# 1_Main.net
KiCad netlist of a schematic drawn in EAGLE
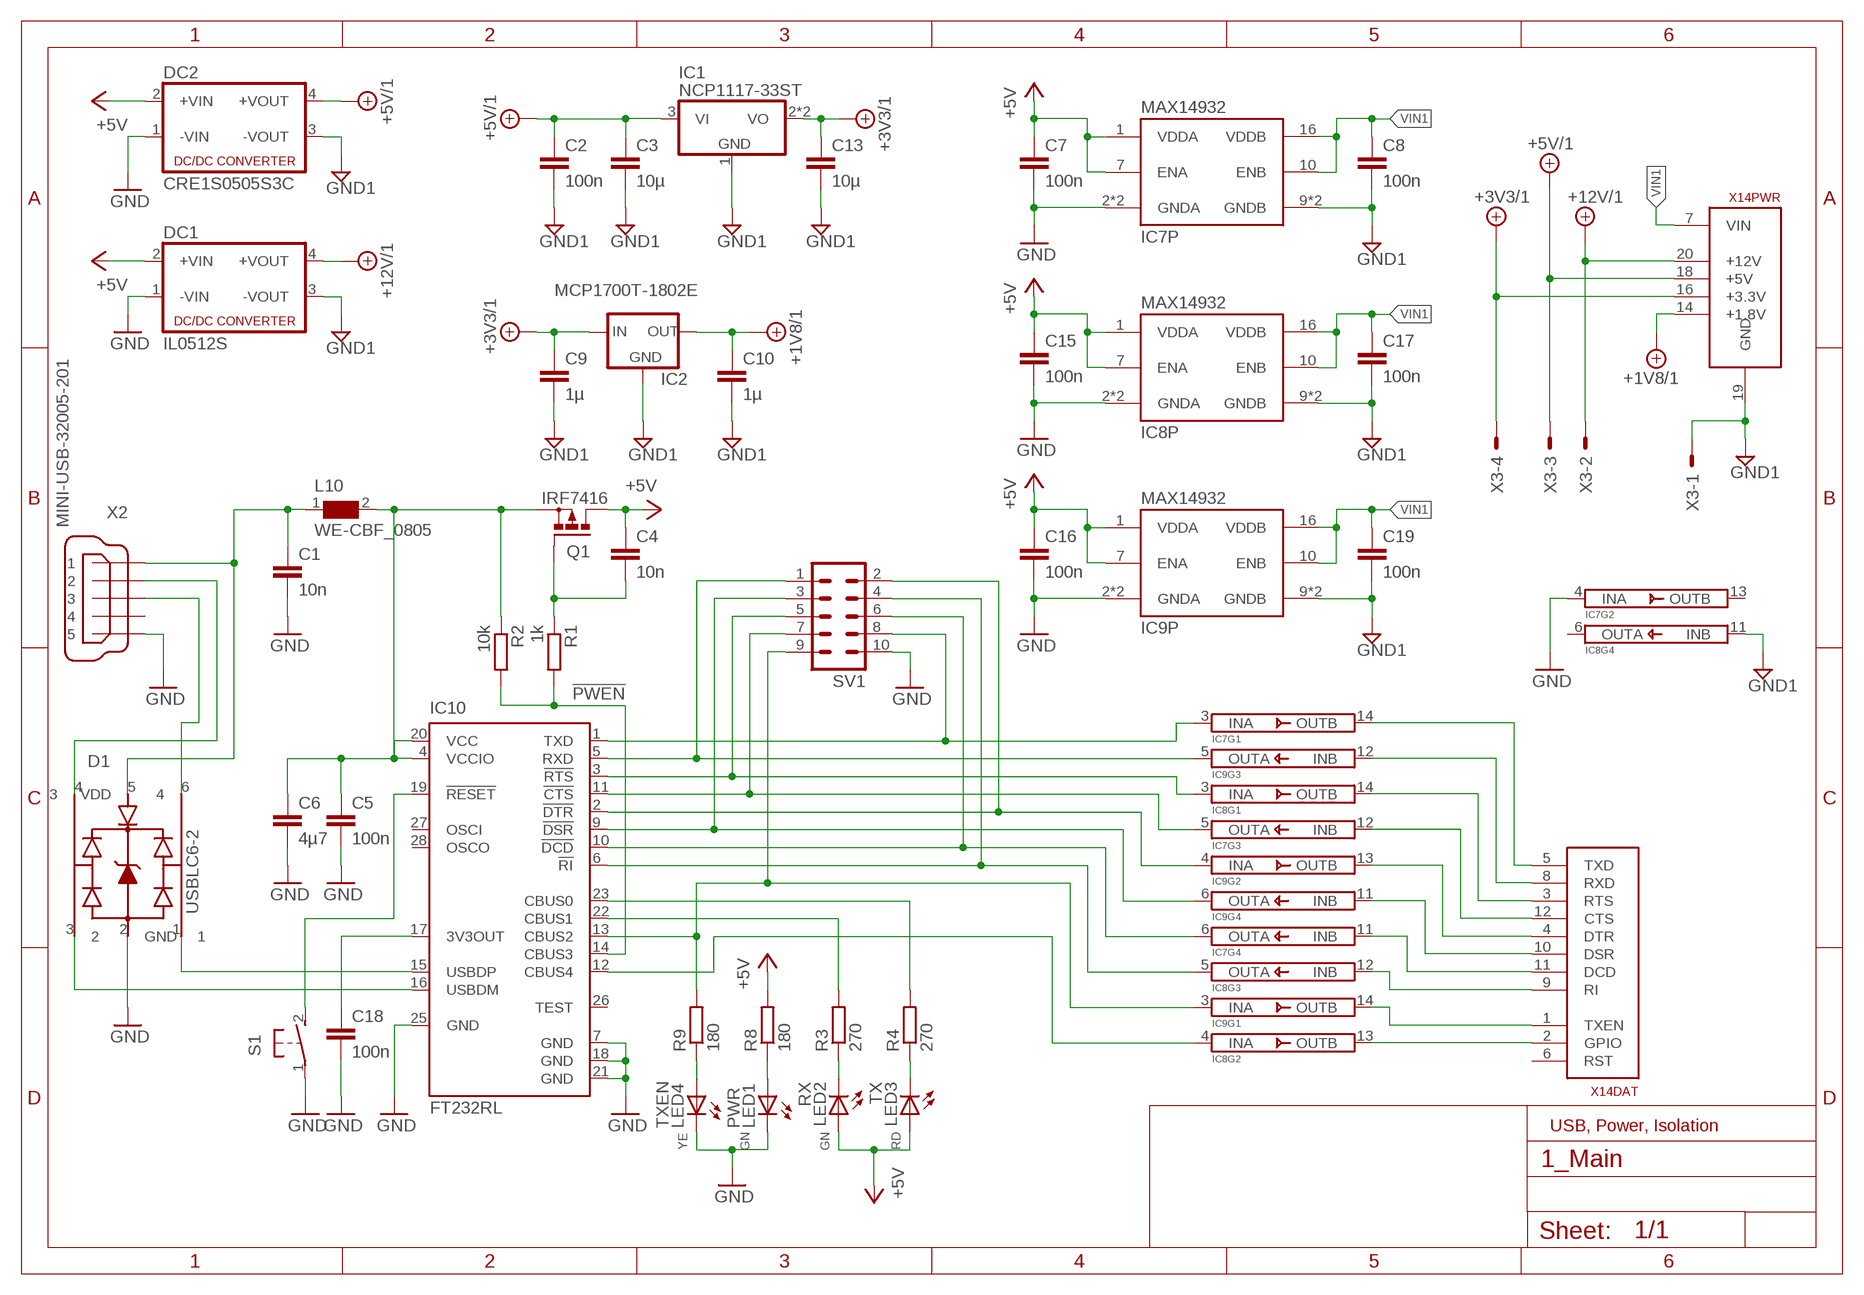
[diagram p0: schematic, sheet 1]

(export (version "E")
  (design (tool "Eeschema 10.0.6"))
  (components
    (comp (ref "C1")
      (value "10n")
      (footprint "eagle-import:C0805")
      (libsource (lib "eagle-import") (part "C-EUC0805"))
    )
    (comp (ref "C2")
      (value "100n")
      (footprint "eagle-import:C0805")
      (libsource (lib "eagle-import") (part "C-EUC0805"))
    )
    (comp (ref "C3")
      (value "10µ")
      (footprint "eagle-import:C0805")
      (libsource (lib "eagle-import") (part "C-EUC0805"))
    )
    (comp (ref "C4")
      (value "10n")
      (footprint "eagle-import:C0805")
      (libsource (lib "eagle-import") (part "C-EUC0805"))
    )
    (comp (ref "C5")
      (value "100n")
      (footprint "eagle-import:C0805")
      (libsource (lib "eagle-import") (part "C-EUC0805"))
    )
    (comp (ref "C6")
      (value "4µ7")
      (footprint "eagle-import:C0805")
      (libsource (lib "eagle-import") (part "C-EUC0805"))
    )
    (comp (ref "C7")
      (value "100n")
      (footprint "eagle-import:C0805")
      (libsource (lib "eagle-import") (part "C-EUC0805"))
    )
    (comp (ref "C8")
      (value "100n")
      (footprint "eagle-import:C0805")
      (libsource (lib "eagle-import") (part "C-EUC0805"))
    )
    (comp (ref "C9")
      (value "1µ")
      (footprint "eagle-import:C0805")
      (libsource (lib "eagle-import") (part "C-EUC0805"))
    )
    (comp (ref "C10")
      (value "1µ")
      (footprint "eagle-import:C0805")
      (libsource (lib "eagle-import") (part "C-EUC0805"))
    )
    (comp (ref "C13")
      (value "10µ")
      (footprint "eagle-import:C0805")
      (libsource (lib "eagle-import") (part "C-EUC0805"))
    )
    (comp (ref "C15")
      (value "100n")
      (footprint "eagle-import:C0805")
      (libsource (lib "eagle-import") (part "C-EUC0805"))
    )
    (comp (ref "C16")
      (value "100n")
      (footprint "eagle-import:C0805")
      (libsource (lib "eagle-import") (part "C-EUC0805"))
    )
    (comp (ref "C17")
      (value "100n")
      (footprint "eagle-import:C0805")
      (libsource (lib "eagle-import") (part "C-EUC0805"))
    )
    (comp (ref "C18")
      (value "100n")
      (footprint "eagle-import:C0805")
      (libsource (lib "eagle-import") (part "C-EUC0805"))
    )
    (comp (ref "C19")
      (value "100n")
      (footprint "eagle-import:C0805")
      (libsource (lib "eagle-import") (part "C-EUC0805"))
    )
    (comp (ref "D1")
      (value "USBLC6-2")
      (footprint "eagle-import:WE-TVS_SOT23-6L")
      (libsource (lib "eagle-import") (part "WE-TVS_82400102"))
    )
    (comp (ref "DC1")
      (value "IL0512S")
      (footprint "eagle-import:NME")
      (fields (field (name "MF") "C & D TECHNOLOGIES, INC") (field (name "MPN") "NME1205D"))
      (libsource (lib "eagle-import") (part "NME"))
    )
    (comp (ref "DC2")
      (value "CRE1S0505S3C")
      (footprint "eagle-import:NME")
      (fields (field (name "MF") "C & D TECHNOLOGIES, INC") (field (name "MPN") "NME1205D"))
      (libsource (lib "eagle-import") (part "NME"))
    )
    (comp (ref "IC1")
      (value "NCP1117-33ST")
      (footprint "eagle-import:SOT223")
      (libsource (lib "eagle-import") (part "NCP1117ST-33"))
    )
    (comp (ref "IC2")
      (value "MCP1700T-1802E")
      (footprint "eagle-import:SOT23")
      (libsource (lib "eagle-import") (part "MCP170X"))
    )
    (comp (ref "IC7")
      (value "MAX14932")
      (footprint "eagle-import:SO16")
      (libsource (lib "eagle-import") (part "MAX14932"))
    )
    (comp (ref "IC8")
      (value "MAX14932")
      (footprint "eagle-import:SO16")
      (libsource (lib "eagle-import") (part "MAX14932"))
    )
    (comp (ref "IC9")
      (value "MAX14932")
      (footprint "eagle-import:SO16")
      (libsource (lib "eagle-import") (part "MAX14932"))
    )
    (comp (ref "IC10")
      (value "FT232RL")
      (footprint "eagle-import:SSOP28")
      (libsource (lib "eagle-import") (part "FT232RL"))
    )
    (comp (ref "L10")
      (value "WE-CBF_0805")
      (footprint "eagle-import:0805")
      (libsource (lib "eagle-import") (part "WE-CBF_0805"))
    )
    (comp (ref "LED1")
      (value "PWR")
      (footprint "eagle-import:CHIPLED_0603")
      (fields (field (name "COLOR") "GN"))
      (libsource (lib "eagle-import") (part "LEDCHIPLED_0603"))
    )
    (comp (ref "LED2")
      (value "RX")
      (footprint "eagle-import:CHIPLED_0603")
      (fields (field (name "COLOR") "GN"))
      (libsource (lib "eagle-import") (part "LEDCHIPLED_0603"))
    )
    (comp (ref "LED3")
      (value "TX")
      (footprint "eagle-import:CHIPLED_0603")
      (fields (field (name "COLOR") "RD"))
      (libsource (lib "eagle-import") (part "LEDCHIPLED_0603"))
    )
    (comp (ref "LED4")
      (value "TXEN")
      (footprint "eagle-import:CHIPLED_0603")
      (fields (field (name "COLOR") "YE"))
      (libsource (lib "eagle-import") (part "LEDCHIPLED_0603"))
    )
    (comp (ref "Q1")
      (value "IRF7416")
      (footprint "eagle-import:SO-08")
      (libsource (lib "eagle-import") (part "P-MOSFET-SO8"))
    )
    (comp (ref "R1")
      (value "1k")
      (footprint "eagle-import:R0805")
      (libsource (lib "eagle-import") (part "R-EU_R0805"))
    )
    (comp (ref "R2")
      (value "10k")
      (footprint "eagle-import:R0805")
      (libsource (lib "eagle-import") (part "R-EU_R0805"))
    )
    (comp (ref "R3")
      (value "270")
      (footprint "eagle-import:R0805")
      (libsource (lib "eagle-import") (part "R-EU_R0805"))
    )
    (comp (ref "R4")
      (value "270")
      (footprint "eagle-import:R0805")
      (libsource (lib "eagle-import") (part "R-EU_R0805"))
    )
    (comp (ref "R8")
      (value "180")
      (footprint "eagle-import:R0805")
      (libsource (lib "eagle-import") (part "R-EU_R0805"))
    )
    (comp (ref "R9")
      (value "180")
      (footprint "eagle-import:R0805")
      (libsource (lib "eagle-import") (part "R-EU_R0805"))
    )
    (comp (ref "S1")
      (value "31-XX")
      (footprint "eagle-import:B3F-31XX")
      (fields (field (name "MPN") "B3F-3100"))
      (libsource (lib "eagle-import") (part "31-XX"))
    )
    (comp (ref "SV1")
      (value "ML10")
      (footprint "eagle-import:ML10")
      (libsource (lib "eagle-import") (part "ML10"))
    )
    (comp (ref "X2")
      (value "MINI-USB-32005-201")
      (footprint "eagle-import:32005-201")
      (libsource (lib "eagle-import") (part "MINI-USB-32005-201"))
    )
    (comp (ref "X3")
      (value "AKL18X-04W")
      (footprint "eagle-import:AKL182-04")
      (libsource (lib "eagle-import") (part "AKL18X-04W"))
    )
    (comp (ref "X14")
      (value "ALLSERIALMM")
      (footprint "eagle-import:MAIN-THT")
      (libsource (lib "eagle-import") (part "ALLSERIALMM"))
    )
  )
  (nets
    (net (code "1") (name "+1V8{slash}1") (class "Default")
      (node (ref "C10") (pin "1") (pinfunction "1_1") (pintype "passive"))
      (node (ref "IC2") (pin "2") (pinfunction "OUT_2") (pintype "passive"))
      (node (ref "X14") (pin "14") (pinfunction "+1.8V_14") (pintype "bidirectional"))
    )
    (net (code "2") (name "+3V3{slash}1") (class "Default")
      (node (ref "C13") (pin "1") (pinfunction "1_1") (pintype "passive"))
      (node (ref "C9") (pin "1") (pinfunction "1_1") (pintype "passive"))
      (node (ref "IC1") (pin "2") (pinfunction "VO_2") (pintype "passive"))
      (node (ref "IC1") (pin "4") (pinfunction "VO_4") (pintype "passive"))
      (node (ref "IC2") (pin "3") (pinfunction "IN_3") (pintype "input"))
      (node (ref "X14") (pin "16") (pinfunction "+3.3V_16") (pintype "bidirectional"))
      (node (ref "X3") (pin "P$4") (pinfunction "S_P$4") (pintype "passive"))
    )
    (net (code "3") (name "+5V") (class "Default")
      (node (ref "C15") (pin "1") (pinfunction "1_1") (pintype "passive"))
      (node (ref "C16") (pin "1") (pinfunction "1_1") (pintype "passive"))
      (node (ref "C4") (pin "1") (pinfunction "1_1") (pintype "passive"))
      (node (ref "C7") (pin "1") (pinfunction "1_1") (pintype "passive"))
      (node (ref "DC1") (pin "2") (pinfunction "+VIN_2") (pintype "passive"))
      (node (ref "DC2") (pin "2") (pinfunction "+VIN_2") (pintype "passive"))
      (node (ref "IC7") (pin "1") (pinfunction "VDDA_1") (pintype "power_in"))
      (node (ref "IC7") (pin "7") (pinfunction "ENA_7") (pintype "input"))
      (node (ref "IC8") (pin "1") (pinfunction "VDDA_1") (pintype "power_in"))
      (node (ref "IC8") (pin "7") (pinfunction "ENA_7") (pintype "input"))
      (node (ref "IC9") (pin "1") (pinfunction "VDDA_1") (pintype "power_in"))
      (node (ref "IC9") (pin "7") (pinfunction "ENA_7") (pintype "input"))
      (node (ref "LED2") (pin "A") (pinfunction "A_A") (pintype "passive"))
      (node (ref "LED3") (pin "A") (pinfunction "A_A") (pintype "passive"))
      (node (ref "Q1") (pin "5") (pinfunction "D_5") (pintype "passive"))
      (node (ref "Q1") (pin "6") (pinfunction "D_6") (pintype "passive"))
      (node (ref "Q1") (pin "7") (pinfunction "D_7") (pintype "passive"))
      (node (ref "Q1") (pin "8") (pinfunction "D_8") (pintype "passive"))
      (node (ref "R8") (pin "2") (pinfunction "2_2") (pintype "passive"))
    )
    (net (code "4") (name "+5V{slash}1") (class "Default")
      (node (ref "C2") (pin "1") (pinfunction "1_1") (pintype "passive"))
      (node (ref "C3") (pin "1") (pinfunction "1_1") (pintype "passive"))
      (node (ref "DC2") (pin "4") (pinfunction "+VOUT_4") (pintype "passive"))
      (node (ref "IC1") (pin "3") (pinfunction "VI_3") (pintype "input"))
      (node (ref "X14") (pin "18") (pinfunction "+5V_18") (pintype "bidirectional"))
      (node (ref "X3") (pin "P$3") (pinfunction "S_P$3") (pintype "passive"))
    )
    (net (code "5") (name "+12V{slash}1") (class "Default")
      (node (ref "DC1") (pin "4") (pinfunction "+VOUT_4") (pintype "passive"))
      (node (ref "X14") (pin "20") (pinfunction "+12V_20") (pintype "bidirectional"))
      (node (ref "X3") (pin "P$2") (pinfunction "S_P$2") (pintype "passive"))
    )
    (net (code "6") (name "/~{PWEN}") (class "Default")
      (node (ref "IC10") (pin "14") (pinfunction "CBUS3_14") (pintype "bidirectional"))
      (node (ref "R1") (pin "2") (pinfunction "2_2") (pintype "passive"))
      (node (ref "R2") (pin "2") (pinfunction "2_2") (pintype "passive"))
    )
    (net (code "7") (name "GND") (class "Default")
      (node (ref "C1") (pin "2") (pinfunction "2_2") (pintype "passive"))
      (node (ref "C15") (pin "2") (pinfunction "2_2") (pintype "passive"))
      (node (ref "C16") (pin "2") (pinfunction "2_2") (pintype "passive"))
      (node (ref "C18") (pin "2") (pinfunction "2_2") (pintype "passive"))
      (node (ref "C5") (pin "2") (pinfunction "2_2") (pintype "passive"))
      (node (ref "C6") (pin "2") (pinfunction "2_2") (pintype "passive"))
      (node (ref "C7") (pin "2") (pinfunction "2_2") (pintype "passive"))
      (node (ref "D1") (pin "2") (pinfunction "GND_2") (pintype "power_in"))
      (node (ref "DC1") (pin "1") (pinfunction "-VIN_1") (pintype "passive"))
      (node (ref "DC2") (pin "1") (pinfunction "-VIN_1") (pintype "passive"))
      (node (ref "IC10") (pin "18") (pinfunction "GND_18") (pintype "power_in"))
      (node (ref "IC10") (pin "21") (pinfunction "GND_21") (pintype "power_in"))
      (node (ref "IC10") (pin "25") (pinfunction "GND_25") (pintype "power_in"))
      (node (ref "IC10") (pin "7") (pinfunction "GND_7") (pintype "power_in"))
      (node (ref "IC7") (pin "2") (pinfunction "GNDA_2") (pintype "power_in"))
      (node (ref "IC7") (pin "4") (pinfunction "INA_4") (pintype "input"))
      (node (ref "IC7") (pin "8") (pinfunction "GNDA_8") (pintype "power_in"))
      (node (ref "IC8") (pin "2") (pinfunction "GNDA_2") (pintype "power_in"))
      (node (ref "IC8") (pin "8") (pinfunction "GNDA_8") (pintype "power_in"))
      (node (ref "IC9") (pin "2") (pinfunction "GNDA_2") (pintype "power_in"))
      (node (ref "IC9") (pin "8") (pinfunction "GNDA_8") (pintype "power_in"))
      (node (ref "LED1") (pin "C") (pinfunction "C_C") (pintype "passive"))
      (node (ref "LED4") (pin "C") (pinfunction "C_C") (pintype "passive"))
      (node (ref "S1") (pin "1") (pinfunction "P_1") (pintype "passive"))
      (node (ref "SV1") (pin "10") (pinfunction "10_10") (pintype "passive"))
      (node (ref "X2") (pin "5") (pinfunction "5_5") (pintype "passive"))
    )
    (net (code "8") (name "GND1") (class "Default")
      (node (ref "C10") (pin "2") (pinfunction "2_2") (pintype "passive"))
      (node (ref "C13") (pin "2") (pinfunction "2_2") (pintype "passive"))
      (node (ref "C17") (pin "2") (pinfunction "2_2") (pintype "passive"))
      (node (ref "C19") (pin "2") (pinfunction "2_2") (pintype "passive"))
      (node (ref "C2") (pin "2") (pinfunction "2_2") (pintype "passive"))
      (node (ref "C3") (pin "2") (pinfunction "2_2") (pintype "passive"))
      (node (ref "C8") (pin "2") (pinfunction "2_2") (pintype "passive"))
      (node (ref "C9") (pin "2") (pinfunction "2_2") (pintype "passive"))
      (node (ref "DC1") (pin "3") (pinfunction "-VOUT_3") (pintype "passive"))
      (node (ref "DC2") (pin "3") (pinfunction "-VOUT_3") (pintype "passive"))
      (node (ref "IC1") (pin "1") (pinfunction "GND_1") (pintype "passive"))
      (node (ref "IC2") (pin "1") (pinfunction "GND_1") (pintype "input"))
      (node (ref "IC7") (pin "15") (pinfunction "GNDB_15") (pintype "power_in"))
      (node (ref "IC7") (pin "9") (pinfunction "GNDB_9") (pintype "power_in"))
      (node (ref "IC8") (pin "11") (pinfunction "INB_11") (pintype "input"))
      (node (ref "IC8") (pin "15") (pinfunction "GNDB_15") (pintype "power_in"))
      (node (ref "IC8") (pin "9") (pinfunction "GNDB_9") (pintype "power_in"))
      (node (ref "IC9") (pin "15") (pinfunction "GNDB_15") (pintype "power_in"))
      (node (ref "IC9") (pin "9") (pinfunction "GNDB_9") (pintype "power_in"))
      (node (ref "X14") (pin "19") (pinfunction "GND_19") (pintype "bidirectional"))
      (node (ref "X3") (pin "P$1") (pinfunction "S_P$1") (pintype "passive"))
    )
    (net (code "9") (name "Net-(D1-2)") (class "Default")
      (node (ref "D1") (pin "3") (pinfunction "2_3") (pintype "passive"))
      (node (ref "IC10") (pin "16") (pinfunction "USBDM_16") (pintype "bidirectional"))
    )
    (net (code "10") (name "Net-(D1-3)") (class "Default")
      (node (ref "D1") (pin "4") (pinfunction "3_4") (pintype "passive"))
      (node (ref "X2") (pin "2") (pinfunction "2_2") (pintype "passive"))
    )
    (net (code "11") (name "Net-(D1-4)") (class "Default")
      (node (ref "D1") (pin "6") (pinfunction "4_6") (pintype "passive"))
      (node (ref "X2") (pin "3") (pinfunction "3_3") (pintype "passive"))
    )
    (net (code "12") (name "Net-(D1-VDD)") (class "Default")
      (node (ref "C1") (pin "1") (pinfunction "1_1") (pintype "passive"))
      (node (ref "D1") (pin "5") (pinfunction "VDD_5") (pintype "power_in"))
      (node (ref "L10") (pin "1") (pinfunction "1_1") (pintype "passive"))
      (node (ref "X2") (pin "1") (pinfunction "1_1") (pintype "passive"))
    )
    (net (code "13") (name "Net-(IC7A-OUTB)") (class "Default")
      (node (ref "IC7") (pin "14") (pinfunction "OUTB_14") (pintype "output"))
      (node (ref "X14") (pin "5") (pinfunction "TXD_5") (pintype "bidirectional"))
    )
    (net (code "14") (name "Net-(IC7C-INB)") (class "Default")
      (node (ref "IC7") (pin "12") (pinfunction "INB_12") (pintype "input"))
      (node (ref "X14") (pin "12") (pinfunction "CTS_12") (pintype "bidirectional"))
    )
    (net (code "15") (name "Net-(IC7D-INB)") (class "Default")
      (node (ref "IC7") (pin "11") (pinfunction "INB_11") (pintype "input"))
      (node (ref "X14") (pin "11") (pinfunction "DCD_11") (pintype "bidirectional"))
    )
    (net (code "16") (name "Net-(IC8A-OUTB)") (class "Default")
      (node (ref "IC8") (pin "14") (pinfunction "OUTB_14") (pintype "output"))
      (node (ref "X14") (pin "3") (pinfunction "RTS_3") (pintype "bidirectional"))
    )
    (net (code "17") (name "Net-(IC8B-OUTB)") (class "Default")
      (node (ref "IC8") (pin "13") (pinfunction "OUTB_13") (pintype "output"))
      (node (ref "X14") (pin "2") (pinfunction "GPIO_2") (pintype "bidirectional"))
    )
    (net (code "18") (name "Net-(IC8C-INB)") (class "Default")
      (node (ref "IC8") (pin "12") (pinfunction "INB_12") (pintype "input"))
      (node (ref "X14") (pin "9") (pinfunction "RI_9") (pintype "bidirectional"))
    )
    (net (code "19") (name "Net-(IC9A-OUTB)") (class "Default")
      (node (ref "IC9") (pin "14") (pinfunction "OUTB_14") (pintype "output"))
      (node (ref "X14") (pin "1") (pinfunction "TXEN_1") (pintype "bidirectional"))
    )
    (net (code "20") (name "Net-(IC9B-OUTB)") (class "Default")
      (node (ref "IC9") (pin "13") (pinfunction "OUTB_13") (pintype "output"))
      (node (ref "X14") (pin "4") (pinfunction "DTR_4") (pintype "bidirectional"))
    )
    (net (code "21") (name "Net-(IC9C-INB)") (class "Default")
      (node (ref "IC9") (pin "12") (pinfunction "INB_12") (pintype "input"))
      (node (ref "X14") (pin "8") (pinfunction "RXD_8") (pintype "bidirectional"))
    )
    (net (code "22") (name "Net-(IC9D-INB)") (class "Default")
      (node (ref "IC9") (pin "11") (pinfunction "INB_11") (pintype "input"))
      (node (ref "X14") (pin "10") (pinfunction "DSR_10") (pintype "bidirectional"))
    )
    (net (code "23") (name "Net-(IC10-3V3OUT)") (class "Default")
      (node (ref "C18") (pin "1") (pinfunction "1_1") (pintype "passive"))
      (node (ref "IC10") (pin "17") (pinfunction "3V3OUT_17") (pintype "output"))
    )
    (net (code "24") (name "Net-(IC10-CBUS0)") (class "Default")
      (node (ref "IC10") (pin "23") (pinfunction "CBUS0_23") (pintype "bidirectional"))
      (node (ref "R4") (pin "2") (pinfunction "2_2") (pintype "passive"))
    )
    (net (code "25") (name "Net-(IC10-CBUS1)") (class "Default")
      (node (ref "IC10") (pin "22") (pinfunction "CBUS1_22") (pintype "bidirectional"))
      (node (ref "R3") (pin "2") (pinfunction "2_2") (pintype "passive"))
    )
    (net (code "26") (name "Net-(IC10-CBUS2)") (class "Default")
      (node (ref "IC10") (pin "13") (pinfunction "CBUS2_13") (pintype "bidirectional"))
      (node (ref "IC9") (pin "3") (pinfunction "INA_3") (pintype "input"))
      (node (ref "R9") (pin "2") (pinfunction "2_2") (pintype "passive"))
      (node (ref "SV1") (pin "9") (pinfunction "9_9") (pintype "passive"))
    )
    (net (code "27") (name "Net-(IC10-CBUS4)") (class "Default")
      (node (ref "IC10") (pin "12") (pinfunction "CBUS4_12") (pintype "bidirectional"))
      (node (ref "IC8") (pin "4") (pinfunction "INA_4") (pintype "input"))
    )
    (net (code "28") (name "Net-(IC10-RXD)") (class "Default")
      (node (ref "IC10") (pin "5") (pinfunction "RXD_5") (pintype "input"))
      (node (ref "IC9") (pin "5") (pinfunction "OUTA_5") (pintype "output"))
      (node (ref "SV1") (pin "1") (pinfunction "1_1") (pintype "passive"))
    )
    (net (code "29") (name "Net-(IC10-TXD)") (class "Default")
      (node (ref "IC10") (pin "1") (pinfunction "TXD_1") (pintype "output"))
      (node (ref "IC7") (pin "3") (pinfunction "INA_3") (pintype "input"))
      (node (ref "SV1") (pin "8") (pinfunction "8_8") (pintype "passive"))
    )
    (net (code "30") (name "Net-(IC10-USBDP)") (class "Default")
      (node (ref "D1") (pin "1") (pinfunction "1_1") (pintype "passive"))
      (node (ref "IC10") (pin "15") (pinfunction "USBDP_15") (pintype "bidirectional"))
    )
    (net (code "31") (name "Net-(IC10-VCC)") (class "Default")
      (node (ref "C5") (pin "1") (pinfunction "1_1") (pintype "passive"))
      (node (ref "C6") (pin "1") (pinfunction "1_1") (pintype "passive"))
      (node (ref "IC10") (pin "20") (pinfunction "VCC_20") (pintype "power_in"))
      (node (ref "IC10") (pin "4") (pinfunction "VCCIO_4") (pintype "power_in"))
      (node (ref "L10") (pin "2") (pinfunction "2_2") (pintype "passive"))
      (node (ref "Q1") (pin "1") (pinfunction "S_1") (pintype "passive"))
      (node (ref "Q1") (pin "2") (pinfunction "S_2") (pintype "passive"))
      (node (ref "Q1") (pin "3") (pinfunction "S_3") (pintype "passive"))
      (node (ref "R2") (pin "1") (pinfunction "1_1") (pintype "passive"))
    )
    (net (code "32") (name "Net-(IC10-~{CTS})") (class "Default")
      (node (ref "IC10") (pin "11") (pinfunction "~{CTS}_11") (pintype "input"))
      (node (ref "IC7") (pin "5") (pinfunction "OUTA_5") (pintype "output"))
      (node (ref "SV1") (pin "7") (pinfunction "7_7") (pintype "passive"))
    )
    (net (code "33") (name "Net-(IC10-~{DCD})") (class "Default")
      (node (ref "IC10") (pin "10") (pinfunction "~{DCD}_10") (pintype "input"))
      (node (ref "IC7") (pin "6") (pinfunction "OUTA_6") (pintype "output"))
      (node (ref "SV1") (pin "6") (pinfunction "6_6") (pintype "passive"))
    )
    (net (code "34") (name "Net-(IC10-~{DSR})") (class "Default")
      (node (ref "IC10") (pin "9") (pinfunction "~{DSR}_9") (pintype "input"))
      (node (ref "IC9") (pin "6") (pinfunction "OUTA_6") (pintype "output"))
      (node (ref "SV1") (pin "3") (pinfunction "3_3") (pintype "passive"))
    )
    (net (code "35") (name "Net-(IC10-~{DTR})") (class "Default")
      (node (ref "IC10") (pin "2") (pinfunction "~{DTR}_2") (pintype "output"))
      (node (ref "IC9") (pin "4") (pinfunction "INA_4") (pintype "input"))
      (node (ref "SV1") (pin "2") (pinfunction "2_2") (pintype "passive"))
    )
    (net (code "36") (name "Net-(IC10-~{RESET})") (class "Default")
      (node (ref "IC10") (pin "19") (pinfunction "~{RESET}_19") (pintype "input"))
      (node (ref "S1") (pin "2") (pinfunction "S_2") (pintype "passive"))
    )
    (net (code "37") (name "Net-(IC10-~{RI})") (class "Default")
      (node (ref "IC10") (pin "6") (pinfunction "~{RI}_6") (pintype "input"))
      (node (ref "IC8") (pin "5") (pinfunction "OUTA_5") (pintype "output"))
      (node (ref "SV1") (pin "4") (pinfunction "4_4") (pintype "passive"))
    )
    (net (code "38") (name "Net-(IC10-~{RTS})") (class "Default")
      (node (ref "IC10") (pin "3") (pinfunction "~{RTS}_3") (pintype "output"))
      (node (ref "IC8") (pin "3") (pinfunction "INA_3") (pintype "input"))
      (node (ref "SV1") (pin "5") (pinfunction "5_5") (pintype "passive"))
    )
    (net (code "39") (name "Net-(LED1-PadA)") (class "Default")
      (node (ref "LED1") (pin "A") (pinfunction "A_A") (pintype "passive"))
      (node (ref "R8") (pin "1") (pinfunction "1_1") (pintype "passive"))
    )
    (net (code "40") (name "Net-(LED2-PadC)") (class "Default")
      (node (ref "LED2") (pin "C") (pinfunction "C_C") (pintype "passive"))
      (node (ref "R3") (pin "1") (pinfunction "1_1") (pintype "passive"))
    )
    (net (code "41") (name "Net-(LED3-PadC)") (class "Default")
      (node (ref "LED3") (pin "C") (pinfunction "C_C") (pintype "passive"))
      (node (ref "R4") (pin "1") (pinfunction "1_1") (pintype "passive"))
    )
    (net (code "42") (name "Net-(LED4-PadA)") (class "Default")
      (node (ref "LED4") (pin "A") (pinfunction "A_A") (pintype "passive"))
      (node (ref "R9") (pin "1") (pinfunction "1_1") (pintype "passive"))
    )
    (net (code "43") (name "Net-(Q1-G)") (class "Default")
      (node (ref "C4") (pin "2") (pinfunction "2_2") (pintype "passive"))
      (node (ref "Q1") (pin "4") (pinfunction "G_4") (pintype "passive"))
      (node (ref "R1") (pin "1") (pinfunction "1_1") (pintype "passive"))
    )
    (net (code "44") (name "VIN1") (class "Default")
      (node (ref "C17") (pin "1") (pinfunction "1_1") (pintype "passive"))
      (node (ref "C19") (pin "1") (pinfunction "1_1") (pintype "passive"))
      (node (ref "C8") (pin "1") (pinfunction "1_1") (pintype "passive"))
      (node (ref "IC7") (pin "10") (pinfunction "ENB_10") (pintype "input"))
      (node (ref "IC7") (pin "16") (pinfunction "VDDB_16") (pintype "power_in"))
      (node (ref "IC8") (pin "10") (pinfunction "ENB_10") (pintype "input"))
      (node (ref "IC8") (pin "16") (pinfunction "VDDB_16") (pintype "power_in"))
      (node (ref "IC9") (pin "10") (pinfunction "ENB_10") (pintype "input"))
      (node (ref "IC9") (pin "16") (pinfunction "VDDB_16") (pintype "power_in"))
      (node (ref "X14") (pin "7") (pinfunction "VIN_7") (pintype "bidirectional"))
    )
    (net (code "45") (name "unconnected-(IC7B-OUTB-Pad13)") (class "Default")
      (node (ref "IC7") (pin "13") (pinfunction "OUTB_13") (pintype "output"))
    )
    (net (code "46") (name "unconnected-(IC8D-OUTA-Pad6)") (class "Default")
      (node (ref "IC8") (pin "6") (pinfunction "OUTA_6") (pintype "output"))
    )
    (net (code "47") (name "unconnected-(IC10-OSCI-Pad27)") (class "Default")
      (node (ref "IC10") (pin "27") (pinfunction "OSCI_27") (pintype "input"))
    )
    (net (code "48") (name "unconnected-(IC10-OSCO-Pad28)") (class "Default")
      (node (ref "IC10") (pin "28") (pinfunction "OSCO_28") (pintype "output"))
    )
    (net (code "49") (name "unconnected-(IC10-TEST-Pad26)") (class "Default")
      (node (ref "IC10") (pin "26") (pinfunction "TEST_26") (pintype "input"))
    )
    (net (code "50") (name "unconnected-(X2-Pad4)") (class "Default")
      (node (ref "X2") (pin "4") (pinfunction "4_4") (pintype "passive"))
    )
    (net (code "51") (name "unconnected-(X14A-RST-Pad6)") (class "Default")
      (node (ref "X14") (pin "6") (pinfunction "RST_6") (pintype "bidirectional"))
    )
  )
)
